# Schematic.net
KiCad netlist of a schematic drawn in EAGLE
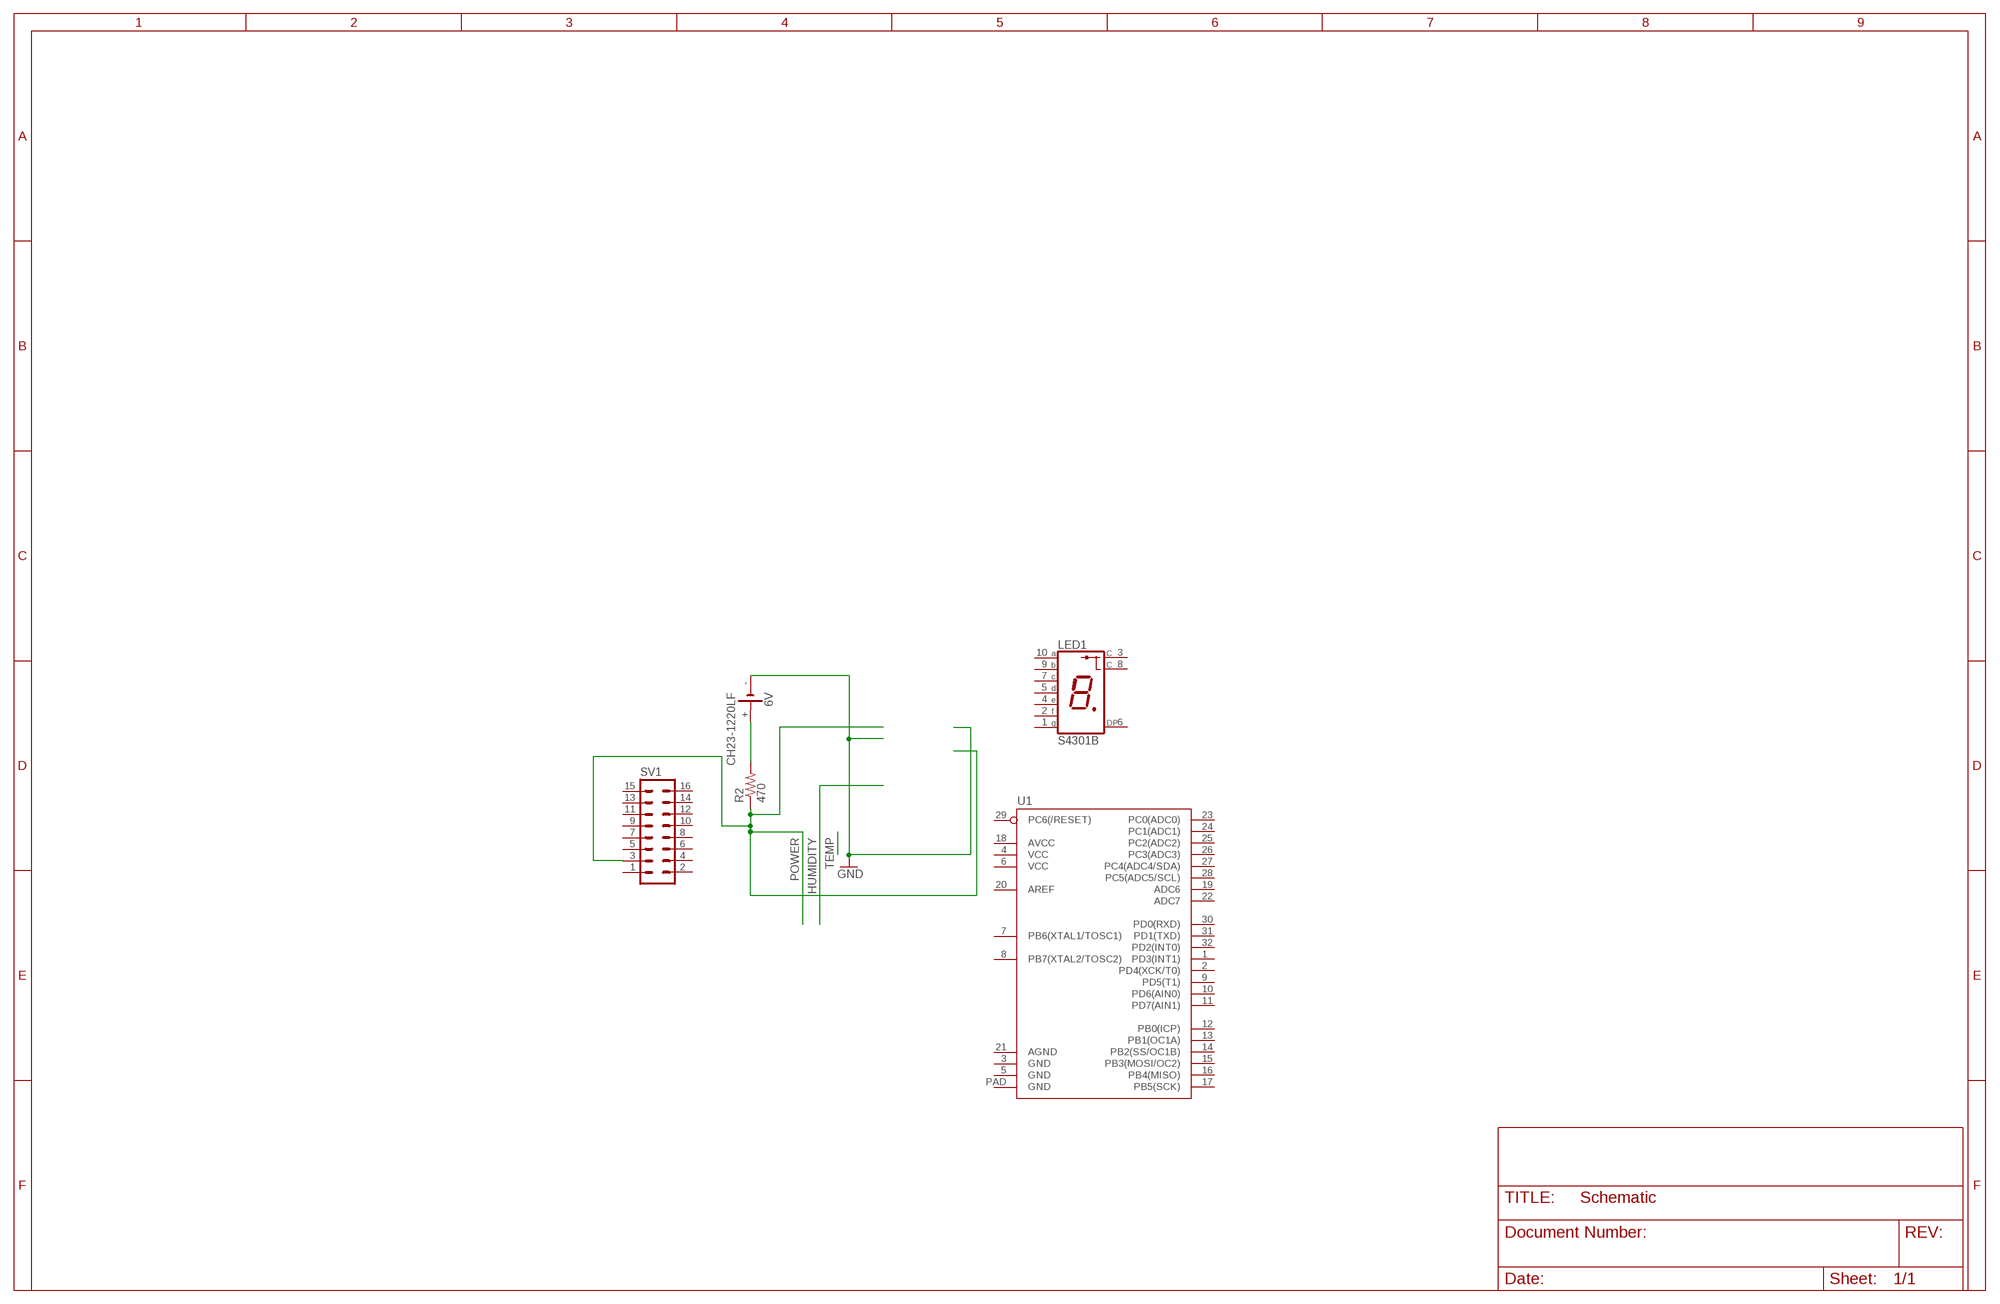
[diagram p0: schematic, sheet 1]

(export (version "E")
  (design (tool "Eeschema 10.0.6"))
  (components
    (comp (ref "6V")
      (value "CH23-1220LF")
      (footprint "eagle-import:CH23-1220LF")
      (libsource (lib "eagle-import") (part "CH23-1220LF"))
    )
    (comp (ref "LED1")
      (value "S4301B")
      (footprint "eagle-import:S4301B")
      (libsource (lib "eagle-import") (part "S4301B"))
    )
    (comp (ref "R2")
      (value "470")
      (footprint "eagle-import:0204V")
      (libsource (lib "eagle-import") (part "R-US_0204/2V"))
    )
    (comp (ref "SV1")
      (value "16PL")
      (footprint "eagle-import:16PL")
      (libsource (lib "eagle-import") (part "16PL"))
    )
    (comp (ref "U1")
      (value "ATMEGA328P_MLFMLF32")
      (footprint "eagle-import:MLF32-PAD")
      (libsource (lib "eagle-import") (part "ATMEGA328P_MLFMLF32"))
    )
  )
  (nets
    (net (code "2") (name "/POWER") (class "Default")
      (node (ref "R2") (pin "1") (pinfunction "1_1") (pintype "passive"))
      (node (ref "SV1") (pin "3") (pinfunction "3_3") (pintype "passive"))
    )
    (net (code "4") (name "GND") (class "Default")
      (node (ref "6V") (pin "-") (pinfunction "-_-") (pintype "passive"))
    )
    (net (code "5") (name "Net-(6V-Pad+)") (class "Default")
      (node (ref "6V") (pin "+") (pinfunction "+_+") (pintype "passive"))
      (node (ref "R2") (pin "2") (pinfunction "2_2") (pintype "passive"))
    )
    (net (code "6") (name "unconnected-(LED1-A-Pad10)") (class "Default")
      (node (ref "LED1") (pin "10") (pinfunction "A_10") (pintype "passive"))
    )
    (net (code "7") (name "unconnected-(LED1-B-Pad9)") (class "Default")
      (node (ref "LED1") (pin "9") (pinfunction "B_9") (pintype "passive"))
    )
    (net (code "8") (name "unconnected-(LED1-C-Pad3)") (class "Default")
      (node (ref "LED1") (pin "3") (pinfunction "C_3") (pintype "passive"))
    )
    (net (code "9") (name "unconnected-(LED1-C-Pad7)") (class "Default")
      (node (ref "LED1") (pin "7") (pinfunction "C_7") (pintype "passive"))
    )
    (net (code "10") (name "unconnected-(LED1-C-Pad8)") (class "Default")
      (node (ref "LED1") (pin "8") (pinfunction "C_8") (pintype "passive"))
    )
    (net (code "11") (name "unconnected-(LED1-D-Pad5)") (class "Default")
      (node (ref "LED1") (pin "5") (pinfunction "D_5") (pintype "passive"))
    )
    (net (code "12") (name "unconnected-(LED1-DP-Pad6)") (class "Default")
      (node (ref "LED1") (pin "6") (pinfunction "DP_6") (pintype "passive"))
    )
    (net (code "13") (name "unconnected-(LED1-E-Pad4)") (class "Default")
      (node (ref "LED1") (pin "4") (pinfunction "E_4") (pintype "passive"))
    )
    (net (code "14") (name "unconnected-(LED1-F-Pad2)") (class "Default")
      (node (ref "LED1") (pin "2") (pinfunction "F_2") (pintype "passive"))
    )
    (net (code "15") (name "unconnected-(LED1-G-Pad1)") (class "Default")
      (node (ref "LED1") (pin "1") (pinfunction "G_1") (pintype "passive"))
    )
    (net (code "16") (name "unconnected-(SV1-Pad1)") (class "Default")
      (node (ref "SV1") (pin "1") (pinfunction "1_1") (pintype "passive"))
    )
    (net (code "17") (name "unconnected-(SV1-Pad2)") (class "Default")
      (node (ref "SV1") (pin "2") (pinfunction "2_2") (pintype "passive"))
    )
    (net (code "18") (name "unconnected-(SV1-Pad4)") (class "Default")
      (node (ref "SV1") (pin "4") (pinfunction "4_4") (pintype "passive"))
    )
    (net (code "19") (name "unconnected-(SV1-Pad5)") (class "Default")
      (node (ref "SV1") (pin "5") (pinfunction "5_5") (pintype "passive"))
    )
    (net (code "20") (name "unconnected-(SV1-Pad6)") (class "Default")
      (node (ref "SV1") (pin "6") (pinfunction "6_6") (pintype "passive"))
    )
    (net (code "21") (name "unconnected-(SV1-Pad7)") (class "Default")
      (node (ref "SV1") (pin "7") (pinfunction "7_7") (pintype "passive"))
    )
    (net (code "22") (name "unconnected-(SV1-Pad8)") (class "Default")
      (node (ref "SV1") (pin "8") (pinfunction "8_8") (pintype "passive"))
    )
    (net (code "23") (name "unconnected-(SV1-Pad9)") (class "Default")
      (node (ref "SV1") (pin "9") (pinfunction "9_9") (pintype "passive"))
    )
    (net (code "24") (name "unconnected-(SV1-Pad10)") (class "Default")
      (node (ref "SV1") (pin "10") (pinfunction "10_10") (pintype "passive"))
    )
    (net (code "25") (name "unconnected-(SV1-Pad11)") (class "Default")
      (node (ref "SV1") (pin "11") (pinfunction "11_11") (pintype "passive"))
    )
    (net (code "26") (name "unconnected-(SV1-Pad12)") (class "Default")
      (node (ref "SV1") (pin "12") (pinfunction "12_12") (pintype "passive"))
    )
    (net (code "27") (name "unconnected-(SV1-Pad13)") (class "Default")
      (node (ref "SV1") (pin "13") (pinfunction "13_13") (pintype "passive"))
    )
    (net (code "28") (name "unconnected-(SV1-Pad14)") (class "Default")
      (node (ref "SV1") (pin "14") (pinfunction "14_14") (pintype "passive"))
    )
    (net (code "29") (name "unconnected-(SV1-Pad15)") (class "Default")
      (node (ref "SV1") (pin "15") (pinfunction "15_15") (pintype "passive"))
    )
    (net (code "30") (name "unconnected-(SV1-Pad16)") (class "Default")
      (node (ref "SV1") (pin "16") (pinfunction "16_16") (pintype "passive"))
    )
    (net (code "31") (name "unconnected-(U1-ADC6-Pad19)") (class "Default")
      (node (ref "U1") (pin "19") (pinfunction "ADC6_19") (pintype "bidirectional"))
    )
    (net (code "32") (name "unconnected-(U1-ADC7-Pad22)") (class "Default")
      (node (ref "U1") (pin "22") (pinfunction "ADC7_22") (pintype "bidirectional"))
    )
    (net (code "33") (name "unconnected-(U1-AGND-Pad21)") (class "Default")
      (node (ref "U1") (pin "21") (pinfunction "AGND_21") (pintype "bidirectional"))
    )
    (net (code "34") (name "unconnected-(U1-AREF-Pad20)") (class "Default")
      (node (ref "U1") (pin "20") (pinfunction "AREF_20") (pintype "bidirectional"))
    )
    (net (code "35") (name "unconnected-(U1-AVCC-Pad18)") (class "Default")
      (node (ref "U1") (pin "18") (pinfunction "AVCC_18") (pintype "bidirectional"))
    )
    (net (code "36") (name "unconnected-(U1-GND-Pad3)") (class "Default")
      (node (ref "U1") (pin "3") (pinfunction "GND_3") (pintype "bidirectional"))
    )
    (net (code "37") (name "unconnected-(U1-GND-Pad5)") (class "Default")
      (node (ref "U1") (pin "5") (pinfunction "GND_5") (pintype "bidirectional"))
    )
    (net (code "38") (name "unconnected-(U1-GND-PadPAD)") (class "Default")
      (node (ref "U1") (pin "PAD") (pinfunction "GND_PAD") (pintype "bidirectional"))
    )
    (net (code "39") (name "unconnected-(U1-PB0(ICP)-Pad12)") (class "Default")
      (node (ref "U1") (pin "12") (pinfunction "PB0(ICP)_12") (pintype "bidirectional"))
    )
    (net (code "40") (name "unconnected-(U1-PB1(OC1A)-Pad13)") (class "Default")
      (node (ref "U1") (pin "13") (pinfunction "PB1(OC1A)_13") (pintype "bidirectional"))
    )
    (net (code "41") (name "unconnected-(U1-PB2(SS{slash}OC1B)-Pad14)") (class "Default")
      (node (ref "U1") (pin "14") (pinfunction "PB2(SS/OC1B)_14") (pintype "bidirectional"))
    )
    (net (code "42") (name "unconnected-(U1-PB3(MOSI{slash}OC2)-Pad15)") (class "Default")
      (node (ref "U1") (pin "15") (pinfunction "PB3(MOSI/OC2)_15") (pintype "bidirectional"))
    )
    (net (code "43") (name "unconnected-(U1-PB4(MISO)-Pad16)") (class "Default")
      (node (ref "U1") (pin "16") (pinfunction "PB4(MISO)_16") (pintype "bidirectional"))
    )
    (net (code "44") (name "unconnected-(U1-PB5(SCK)-Pad17)") (class "Default")
      (node (ref "U1") (pin "17") (pinfunction "PB5(SCK)_17") (pintype "bidirectional"))
    )
    (net (code "45") (name "unconnected-(U1-PB6(XTAL1{slash}TOSC1)-Pad7)") (class "Default")
      (node (ref "U1") (pin "7") (pinfunction "PB6(XTAL1/TOSC1)_7") (pintype "bidirectional"))
    )
    (net (code "46") (name "unconnected-(U1-PB7(XTAL2{slash}TOSC2)-Pad8)") (class "Default")
      (node (ref "U1") (pin "8") (pinfunction "PB7(XTAL2/TOSC2)_8") (pintype "bidirectional"))
    )
    (net (code "47") (name "unconnected-(U1-PC0(ADC0)-Pad23)") (class "Default")
      (node (ref "U1") (pin "23") (pinfunction "PC0(ADC0)_23") (pintype "bidirectional"))
    )
    (net (code "48") (name "unconnected-(U1-PC1(ADC1)-Pad24)") (class "Default")
      (node (ref "U1") (pin "24") (pinfunction "PC1(ADC1)_24") (pintype "bidirectional"))
    )
    (net (code "49") (name "unconnected-(U1-PC2(ADC2)-Pad25)") (class "Default")
      (node (ref "U1") (pin "25") (pinfunction "PC2(ADC2)_25") (pintype "bidirectional"))
    )
    (net (code "50") (name "unconnected-(U1-PC3(ADC3)-Pad26)") (class "Default")
      (node (ref "U1") (pin "26") (pinfunction "PC3(ADC3)_26") (pintype "bidirectional"))
    )
    (net (code "51") (name "unconnected-(U1-PC4(ADC4{slash}SDA)-Pad27)") (class "Default")
      (node (ref "U1") (pin "27") (pinfunction "PC4(ADC4/SDA)_27") (pintype "bidirectional"))
    )
    (net (code "52") (name "unconnected-(U1-PC5(ADC5{slash}SCL)-Pad28)") (class "Default")
      (node (ref "U1") (pin "28") (pinfunction "PC5(ADC5/SCL)_28") (pintype "bidirectional"))
    )
    (net (code "53") (name "unconnected-(U1-PC6({slash}RESET)-Pad29)") (class "Default")
      (node (ref "U1") (pin "29") (pinfunction "PC6(/RESET)_29") (pintype "bidirectional"))
    )
    (net (code "54") (name "unconnected-(U1-PD0(RXD)-Pad30)") (class "Default")
      (node (ref "U1") (pin "30") (pinfunction "PD0(RXD)_30") (pintype "bidirectional"))
    )
    (net (code "55") (name "unconnected-(U1-PD1(TXD)-Pad31)") (class "Default")
      (node (ref "U1") (pin "31") (pinfunction "PD1(TXD)_31") (pintype "bidirectional"))
    )
    (net (code "56") (name "unconnected-(U1-PD2(INT0)-Pad32)") (class "Default")
      (node (ref "U1") (pin "32") (pinfunction "PD2(INT0)_32") (pintype "bidirectional"))
    )
    (net (code "57") (name "unconnected-(U1-PD3(INT1)-Pad1)") (class "Default")
      (node (ref "U1") (pin "1") (pinfunction "PD3(INT1)_1") (pintype "bidirectional"))
    )
    (net (code "58") (name "unconnected-(U1-PD4(XCK{slash}T0)-Pad2)") (class "Default")
      (node (ref "U1") (pin "2") (pinfunction "PD4(XCK/T0)_2") (pintype "bidirectional"))
    )
    (net (code "59") (name "unconnected-(U1-PD5(T1)-Pad9)") (class "Default")
      (node (ref "U1") (pin "9") (pinfunction "PD5(T1)_9") (pintype "bidirectional"))
    )
    (net (code "60") (name "unconnected-(U1-PD6(AIN0)-Pad10)") (class "Default")
      (node (ref "U1") (pin "10") (pinfunction "PD6(AIN0)_10") (pintype "bidirectional"))
    )
    (net (code "61") (name "unconnected-(U1-PD7(AIN1)-Pad11)") (class "Default")
      (node (ref "U1") (pin "11") (pinfunction "PD7(AIN1)_11") (pintype "bidirectional"))
    )
    (net (code "62") (name "unconnected-(U1-VCC-Pad4)") (class "Default")
      (node (ref "U1") (pin "4") (pinfunction "VCC_4") (pintype "bidirectional"))
    )
    (net (code "63") (name "unconnected-(U1-VCC-Pad6)") (class "Default")
      (node (ref "U1") (pin "6") (pinfunction "VCC_6") (pintype "bidirectional"))
    )
  )
)
